# FPGA_PSIO.net
KiCad netlist of a schematic drawn in Altium Designer
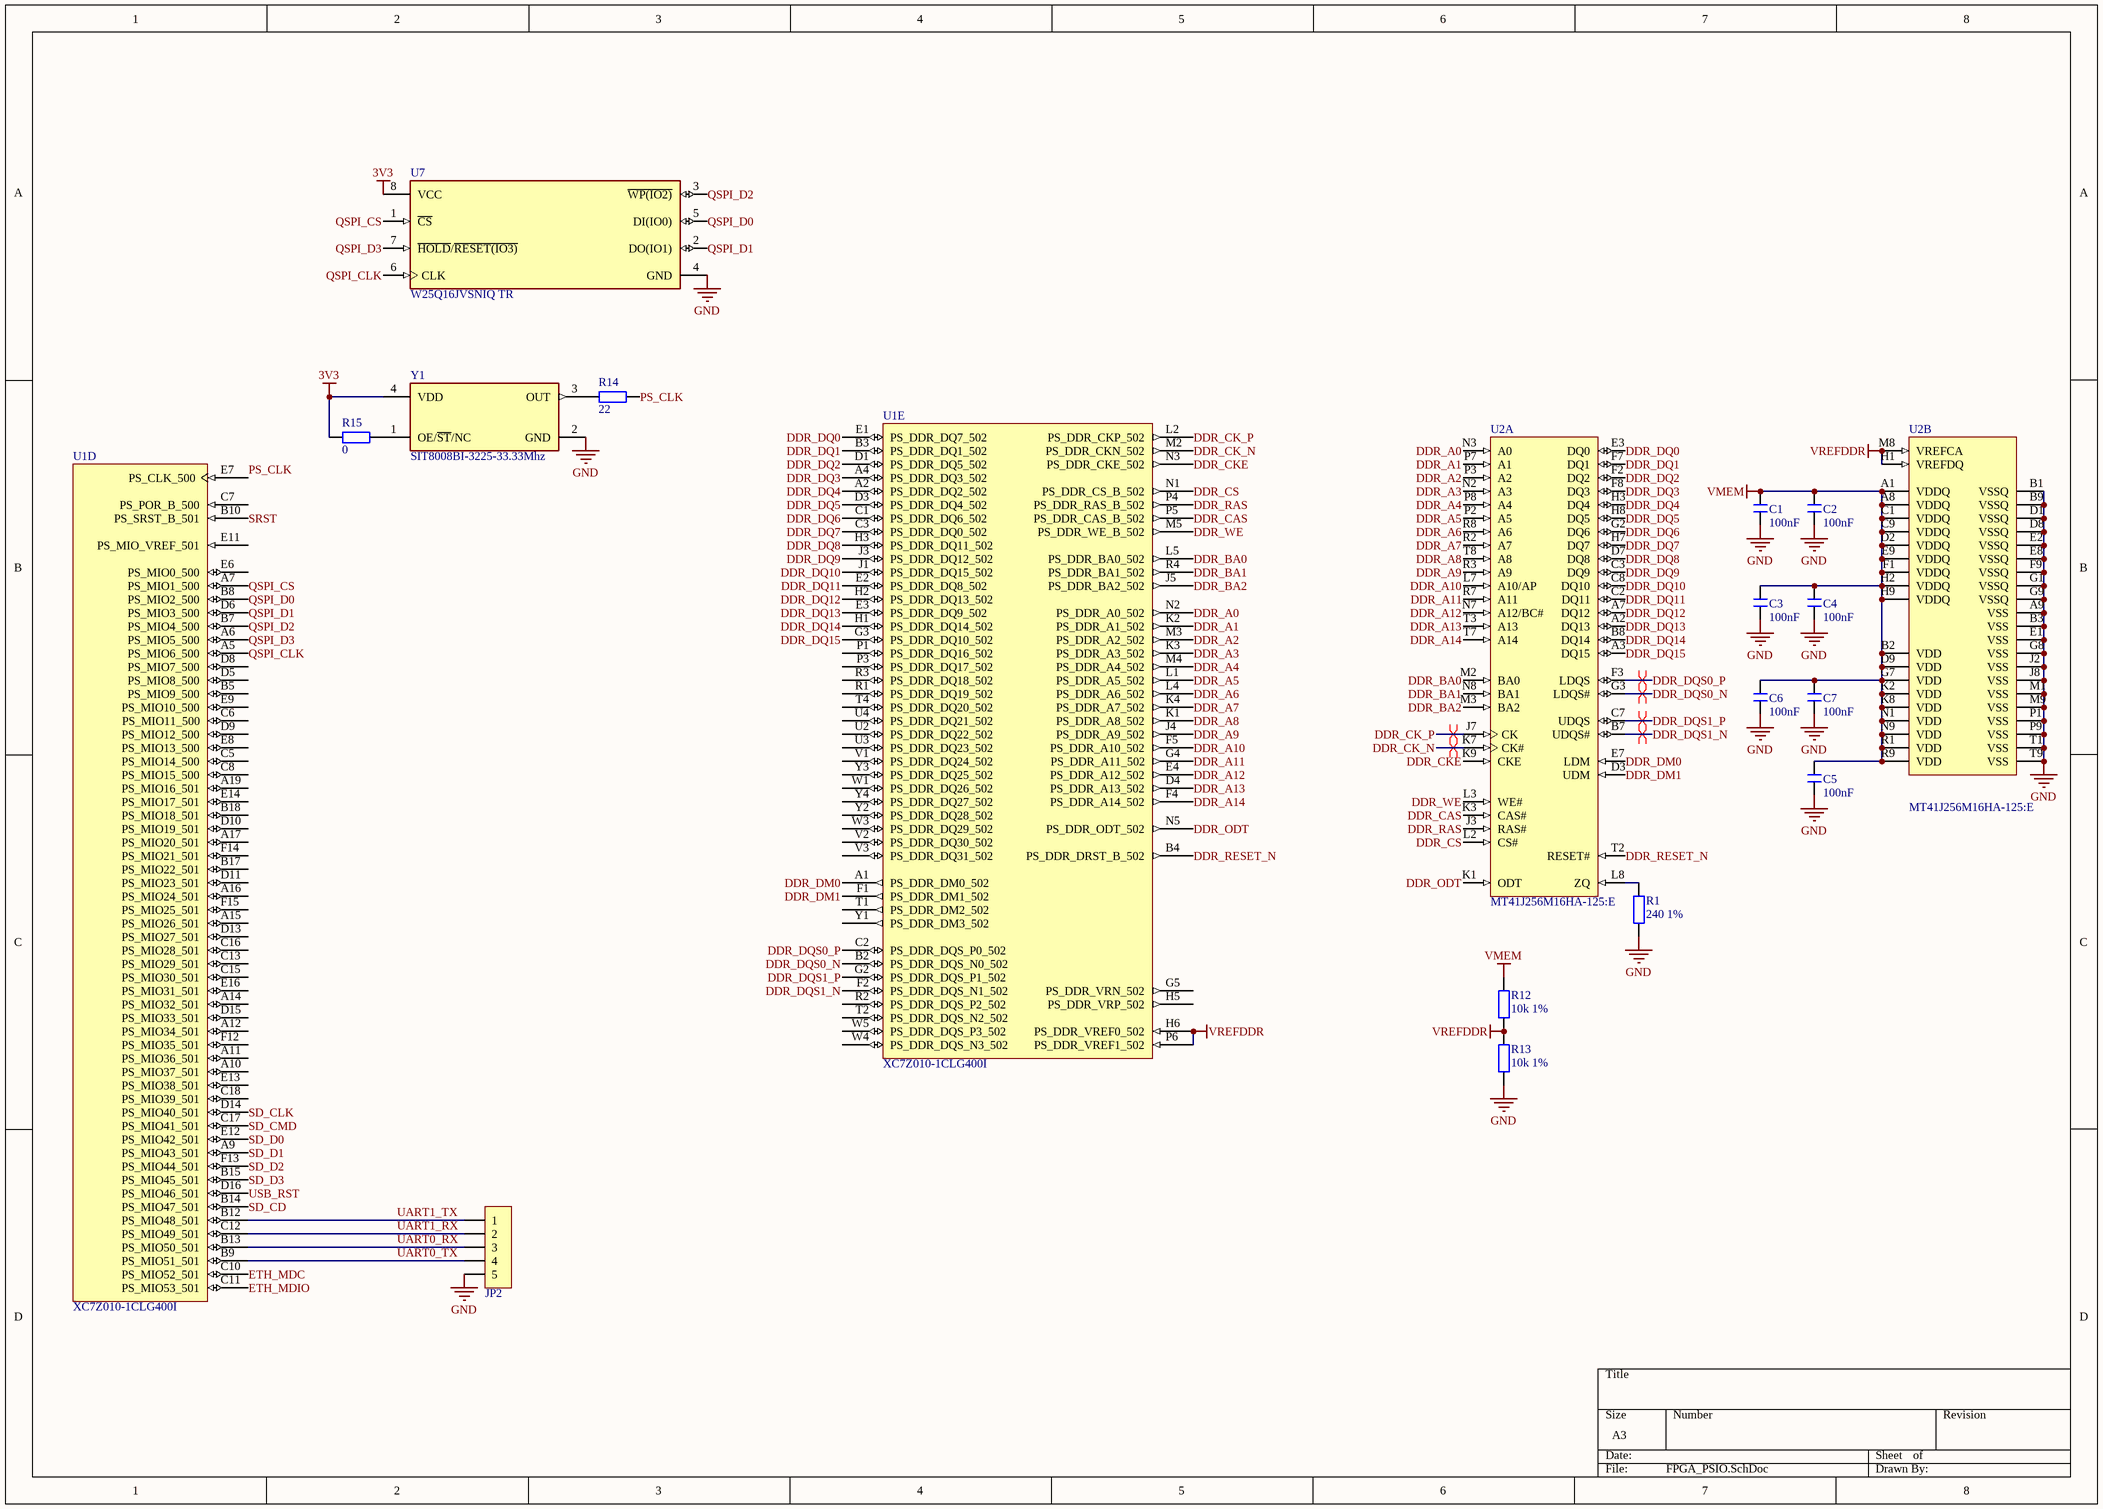
[diagram p0: FPGA_PSIO.SchDoc]

(export (version "E")
  (design (tool "Eeschema 10.0.6"))
  (components
    (comp (ref "C1") (value "100nF") (footprint "C0402") (libsource (lib "Passive") (part "C")))
    (comp (ref "C2") (value "100nF") (footprint "C0402") (libsource (lib "Passive") (part "C")))
    (comp (ref "C3") (value "100nF") (footprint "C0402") (libsource (lib "Passive") (part "C")))
    (comp (ref "C4") (value "100nF") (footprint "C0402") (libsource (lib "Passive") (part "C")))
    (comp (ref "C5") (value "100nF") (footprint "C0402") (libsource (lib "Passive") (part "C")))
    (comp (ref "C6") (value "100nF") (footprint "C0402") (libsource (lib "Passive") (part "C")))
    (comp (ref "C7") (value "100nF") (footprint "C0402") (libsource (lib "Passive") (part "C")))
    (comp (ref "JP2")
      (value "HDR-1X5")
      (footprint "HDR2.54-LI-5P")
      (description "5P接插件")
      (fields (field (name "版权归属") "源创客"))
      (libsource (lib "Pin2.54") (part "Header 5"))
    )
    (comp (ref "R1") (value "240 1%") (footprint "R0603") (libsource (lib "Passive") (part "R")))
    (comp (ref "R12") (value "10k 1%") (footprint "R0402") (libsource (lib "Passive") (part "R")))
    (comp (ref "R13") (value "10k 1%") (footprint "R0402") (libsource (lib "Passive") (part "R")))
    (comp (ref "R14") (value "22") (footprint "R0402") (libsource (lib "Passive") (part "R")))
    (comp (ref "R15") (value "0") (footprint "R0402") (libsource (lib "Passive") (part "R")))
    (comp (ref "U1")
      (value "XC7Z010-1CLG400I")
      (footprint "CLG400")
      (fields (field (name "GENERIC PART NUMBER") "XC7Z010"))
      (libsource (lib "Altium Content Vault") (part "XNLX-XC7Z010-CLG400"))
    )
    (comp (ref "U2")
      (value "MT41J256M16HA-125:E")
      (footprint "MICT-HA-96")
      (description "4 Gb DDR3-1600 SDRAM, 256 Mb x 16, 1.25 ns, 1.5 V, 0 to 95 degC, 96-Ball FBGA, Pb-Free")
      (fields (field (name "MANUFACTURER") "Micron"))
      (libsource (lib "Altium Content Vault") (part "MICT-MT41J256M16HA-96"))
    )
    (comp (ref "U7")
      (value "W25Q16JVSNIQ TR")
      (footprint "FP-SN-MFG")
      (description "IC FLASH 16MBIT SPI/QUAD 8SOIC")
      (libsource (lib "Altium Content Vault") (part "7098f54d44eb8b75f85f137256f9325"))
    )
    (comp (ref "Y1")
      (value "SIT8008BI-3225-33.33Mhz")
      (footprint "FP-SiT8008-2-MFG")
      (libsource (lib "Altium Content Vault") (part "5cf877c3599e51cbf79feac712dbb68"))
    )
  )
  (nets
    (net (code "2") (name "/DDR_A0") (class "Default")
      (node (ref "U1") (pin "N2") (pinfunction "PS_DDR_A0_502_N2") (pintype "output"))
      (node (ref "U2") (pin "N3") (pinfunction "A0_N3") (pintype "input"))
    )
    (net (code "3") (name "/DDR_A1") (class "Default")
      (node (ref "U1") (pin "K2") (pinfunction "PS_DDR_A1_502_K2") (pintype "output"))
      (node (ref "U2") (pin "P7") (pinfunction "A1_P7") (pintype "input"))
    )
    (net (code "4") (name "/DDR_A2") (class "Default")
      (node (ref "U1") (pin "M3") (pinfunction "PS_DDR_A2_502_M3") (pintype "output"))
      (node (ref "U2") (pin "P3") (pinfunction "A2_P3") (pintype "input"))
    )
    (net (code "5") (name "/DDR_A3") (class "Default")
      (node (ref "U1") (pin "K3") (pinfunction "PS_DDR_A3_502_K3") (pintype "output"))
      (node (ref "U2") (pin "N2") (pinfunction "A3_N2") (pintype "input"))
    )
    (net (code "6") (name "/DDR_A4") (class "Default")
      (node (ref "U1") (pin "M4") (pinfunction "PS_DDR_A4_502_M4") (pintype "output"))
      (node (ref "U2") (pin "P8") (pinfunction "A4_P8") (pintype "input"))
    )
    (net (code "7") (name "/DDR_A5") (class "Default")
      (node (ref "U1") (pin "L1") (pinfunction "PS_DDR_A5_502_L1") (pintype "output"))
      (node (ref "U2") (pin "P2") (pinfunction "A5_P2") (pintype "input"))
    )
    (net (code "8") (name "/DDR_A6") (class "Default")
      (node (ref "U1") (pin "L4") (pinfunction "PS_DDR_A6_502_L4") (pintype "output"))
      (node (ref "U2") (pin "R8") (pinfunction "A6_R8") (pintype "input"))
    )
    (net (code "9") (name "/DDR_A7") (class "Default")
      (node (ref "U1") (pin "K4") (pinfunction "PS_DDR_A7_502_K4") (pintype "output"))
      (node (ref "U2") (pin "R2") (pinfunction "A7_R2") (pintype "input"))
    )
    (net (code "10") (name "/DDR_A8") (class "Default")
      (node (ref "U1") (pin "K1") (pinfunction "PS_DDR_A8_502_K1") (pintype "output"))
      (node (ref "U2") (pin "T8") (pinfunction "A8_T8") (pintype "input"))
    )
    (net (code "11") (name "/DDR_A9") (class "Default")
      (node (ref "U1") (pin "J4") (pinfunction "PS_DDR_A9_502_J4") (pintype "output"))
      (node (ref "U2") (pin "R3") (pinfunction "A9_R3") (pintype "input"))
    )
    (net (code "12") (name "/DDR_A10") (class "Default")
      (node (ref "U1") (pin "F5") (pinfunction "PS_DDR_A10_502_F5") (pintype "output"))
      (node (ref "U2") (pin "L7") (pinfunction "A10/AP_L7") (pintype "input"))
    )
    (net (code "13") (name "/DDR_A11") (class "Default")
      (node (ref "U1") (pin "G4") (pinfunction "PS_DDR_A11_502_G4") (pintype "output"))
      (node (ref "U2") (pin "R7") (pinfunction "A11_R7") (pintype "input"))
    )
    (net (code "14") (name "/DDR_A12") (class "Default")
      (node (ref "U1") (pin "E4") (pinfunction "PS_DDR_A12_502_E4") (pintype "output"))
      (node (ref "U2") (pin "N7") (pinfunction "A12/BC#_N7") (pintype "input"))
    )
    (net (code "15") (name "/DDR_A13") (class "Default")
      (node (ref "U1") (pin "D4") (pinfunction "PS_DDR_A13_502_D4") (pintype "output"))
      (node (ref "U2") (pin "T3") (pinfunction "A13_T3") (pintype "input"))
    )
    (net (code "16") (name "/DDR_A14") (class "Default")
      (node (ref "U1") (pin "F4") (pinfunction "PS_DDR_A14_502_F4") (pintype "output"))
      (node (ref "U2") (pin "T7") (pinfunction "A14_T7") (pintype "input"))
    )
    (net (code "17") (name "/DDR_BA0") (class "Default")
      (node (ref "U1") (pin "L5") (pinfunction "PS_DDR_BA0_502_L5") (pintype "output"))
      (node (ref "U2") (pin "M2") (pinfunction "BA0_M2") (pintype "input"))
    )
    (net (code "18") (name "/DDR_BA1") (class "Default")
      (node (ref "U1") (pin "R4") (pinfunction "PS_DDR_BA1_502_R4") (pintype "output"))
      (node (ref "U2") (pin "N8") (pinfunction "BA1_N8") (pintype "input"))
    )
    (net (code "19") (name "/DDR_BA2") (class "Default")
      (node (ref "U1") (pin "J5") (pinfunction "PS_DDR_BA2_502_J5") (pintype "output"))
      (node (ref "U2") (pin "M3") (pinfunction "BA2_M3") (pintype "input"))
    )
    (net (code "20") (name "/DDR_CAS") (class "Default")
      (node (ref "U1") (pin "P5") (pinfunction "PS_DDR_CAS_B_502_P5") (pintype "output"))
      (node (ref "U2") (pin "K3") (pinfunction "CAS#_K3") (pintype "input"))
    )
    (net (code "21") (name "/DDR_CKE") (class "Default")
      (node (ref "U1") (pin "N3") (pinfunction "PS_DDR_CKE_502_N3") (pintype "output"))
      (node (ref "U2") (pin "K9") (pinfunction "CKE_K9") (pintype "input"))
    )
    (net (code "22") (name "/DDR_CK_N") (class "Default")
      (node (ref "U1") (pin "M2") (pinfunction "PS_DDR_CKN_502_M2") (pintype "output"))
      (node (ref "U2") (pin "K7") (pinfunction "CK#_K7") (pintype "input"))
    )
    (net (code "23") (name "/DDR_CK_P") (class "Default")
      (node (ref "U1") (pin "L2") (pinfunction "PS_DDR_CKP_502_L2") (pintype "output"))
      (node (ref "U2") (pin "J7") (pinfunction "CK_J7") (pintype "input"))
    )
    (net (code "24") (name "/DDR_CS") (class "Default")
      (node (ref "U1") (pin "N1") (pinfunction "PS_DDR_CS_B_502_N1") (pintype "output"))
      (node (ref "U2") (pin "L2") (pinfunction "CS#_L2") (pintype "input"))
    )
    (net (code "25") (name "/DDR_DM0") (class "Default")
      (node (ref "U1") (pin "A1") (pinfunction "PS_DDR_DM0_502_A1") (pintype "output"))
      (node (ref "U2") (pin "E7") (pinfunction "LDM_E7") (pintype "input"))
    )
    (net (code "26") (name "/DDR_DM1") (class "Default")
      (node (ref "U1") (pin "F1") (pinfunction "PS_DDR_DM1_502_F1") (pintype "output"))
      (node (ref "U2") (pin "D3") (pinfunction "UDM_D3") (pintype "input"))
    )
    (net (code "27") (name "/DDR_DQ0") (class "Default")
      (node (ref "U1") (pin "E1") (pinfunction "PS_DDR_DQ7_502_E1") (pintype "bidirectional"))
      (node (ref "U2") (pin "E3") (pinfunction "DQ0_E3") (pintype "bidirectional"))
    )
    (net (code "28") (name "/DDR_DQ1") (class "Default")
      (node (ref "U1") (pin "B3") (pinfunction "PS_DDR_DQ1_502_B3") (pintype "bidirectional"))
      (node (ref "U2") (pin "F7") (pinfunction "DQ1_F7") (pintype "bidirectional"))
    )
    (net (code "29") (name "/DDR_DQ2") (class "Default")
      (node (ref "U1") (pin "D1") (pinfunction "PS_DDR_DQ5_502_D1") (pintype "bidirectional"))
      (node (ref "U2") (pin "F2") (pinfunction "DQ2_F2") (pintype "bidirectional"))
    )
    (net (code "30") (name "/DDR_DQ3") (class "Default")
      (node (ref "U1") (pin "A4") (pinfunction "PS_DDR_DQ3_502_A4") (pintype "bidirectional"))
      (node (ref "U2") (pin "F8") (pinfunction "DQ3_F8") (pintype "bidirectional"))
    )
    (net (code "31") (name "/DDR_DQ4") (class "Default")
      (node (ref "U1") (pin "A2") (pinfunction "PS_DDR_DQ2_502_A2") (pintype "bidirectional"))
      (node (ref "U2") (pin "H3") (pinfunction "DQ4_H3") (pintype "bidirectional"))
    )
    (net (code "32") (name "/DDR_DQ5") (class "Default")
      (node (ref "U1") (pin "D3") (pinfunction "PS_DDR_DQ4_502_D3") (pintype "bidirectional"))
      (node (ref "U2") (pin "H8") (pinfunction "DQ5_H8") (pintype "bidirectional"))
    )
    (net (code "33") (name "/DDR_DQ6") (class "Default")
      (node (ref "U1") (pin "C1") (pinfunction "PS_DDR_DQ6_502_C1") (pintype "bidirectional"))
      (node (ref "U2") (pin "G2") (pinfunction "DQ6_G2") (pintype "bidirectional"))
    )
    (net (code "34") (name "/DDR_DQ7") (class "Default")
      (node (ref "U1") (pin "C3") (pinfunction "PS_DDR_DQ0_502_C3") (pintype "bidirectional"))
      (node (ref "U2") (pin "H7") (pinfunction "DQ7_H7") (pintype "bidirectional"))
    )
    (net (code "35") (name "/DDR_DQ8") (class "Default")
      (node (ref "U1") (pin "H3") (pinfunction "PS_DDR_DQ11_502_H3") (pintype "bidirectional"))
      (node (ref "U2") (pin "D7") (pinfunction "DQ8_D7") (pintype "bidirectional"))
    )
    (net (code "36") (name "/DDR_DQ9") (class "Default")
      (node (ref "U1") (pin "J3") (pinfunction "PS_DDR_DQ12_502_J3") (pintype "bidirectional"))
      (node (ref "U2") (pin "C3") (pinfunction "DQ9_C3") (pintype "bidirectional"))
    )
    (net (code "37") (name "/DDR_DQ10") (class "Default")
      (node (ref "U1") (pin "J1") (pinfunction "PS_DDR_DQ15_502_J1") (pintype "bidirectional"))
      (node (ref "U2") (pin "C8") (pinfunction "DQ10_C8") (pintype "bidirectional"))
    )
    (net (code "38") (name "/DDR_DQ11") (class "Default")
      (node (ref "U1") (pin "E2") (pinfunction "PS_DDR_DQ8_502_E2") (pintype "bidirectional"))
      (node (ref "U2") (pin "C2") (pinfunction "DQ11_C2") (pintype "bidirectional"))
    )
    (net (code "39") (name "/DDR_DQ12") (class "Default")
      (node (ref "U1") (pin "H2") (pinfunction "PS_DDR_DQ13_502_H2") (pintype "bidirectional"))
      (node (ref "U2") (pin "A7") (pinfunction "DQ12_A7") (pintype "bidirectional"))
    )
    (net (code "40") (name "/DDR_DQ13") (class "Default")
      (node (ref "U1") (pin "E3") (pinfunction "PS_DDR_DQ9_502_E3") (pintype "bidirectional"))
      (node (ref "U2") (pin "A2") (pinfunction "DQ13_A2") (pintype "bidirectional"))
    )
    (net (code "41") (name "/DDR_DQ14") (class "Default")
      (node (ref "U1") (pin "H1") (pinfunction "PS_DDR_DQ14_502_H1") (pintype "bidirectional"))
      (node (ref "U2") (pin "B8") (pinfunction "DQ14_B8") (pintype "bidirectional"))
    )
    (net (code "42") (name "/DDR_DQ15") (class "Default")
      (node (ref "U1") (pin "G3") (pinfunction "PS_DDR_DQ10_502_G3") (pintype "bidirectional"))
      (node (ref "U2") (pin "A3") (pinfunction "DQ15_A3") (pintype "bidirectional"))
    )
    (net (code "43") (name "/DDR_DQS0_N") (class "Default")
      (node (ref "U1") (pin "B2") (pinfunction "PS_DDR_DQS_N0_502_B2") (pintype "bidirectional"))
      (node (ref "U2") (pin "G3") (pinfunction "LDQS#_G3") (pintype "bidirectional"))
    )
    (net (code "44") (name "/DDR_DQS0_P") (class "Default")
      (node (ref "U1") (pin "C2") (pinfunction "PS_DDR_DQS_P0_502_C2") (pintype "bidirectional"))
      (node (ref "U2") (pin "F3") (pinfunction "LDQS_F3") (pintype "bidirectional"))
    )
    (net (code "45") (name "/DDR_DQS1_N") (class "Default")
      (node (ref "U1") (pin "F2") (pinfunction "PS_DDR_DQS_N1_502_F2") (pintype "bidirectional"))
      (node (ref "U2") (pin "B7") (pinfunction "UDQS#_B7") (pintype "bidirectional"))
    )
    (net (code "46") (name "/DDR_DQS1_P") (class "Default")
      (node (ref "U1") (pin "G2") (pinfunction "PS_DDR_DQS_P1_502_G2") (pintype "bidirectional"))
      (node (ref "U2") (pin "C7") (pinfunction "UDQS_C7") (pintype "bidirectional"))
    )
    (net (code "47") (name "/DDR_ODT") (class "Default")
      (node (ref "U1") (pin "N5") (pinfunction "PS_DDR_ODT_502_N5") (pintype "output"))
      (node (ref "U2") (pin "K1") (pinfunction "ODT_K1") (pintype "input"))
    )
    (net (code "48") (name "/DDR_RAS") (class "Default")
      (node (ref "U1") (pin "P4") (pinfunction "PS_DDR_RAS_B_502_P4") (pintype "output"))
      (node (ref "U2") (pin "J3") (pinfunction "RAS#_J3") (pintype "input"))
    )
    (net (code "49") (name "/DDR_RESET_N") (class "Default")
      (node (ref "U1") (pin "B4") (pinfunction "PS_DDR_DRST_B_502_B4") (pintype "output"))
      (node (ref "U2") (pin "T2") (pinfunction "RESET#_T2") (pintype "input"))
    )
    (net (code "50") (name "/DDR_WE") (class "Default")
      (node (ref "U1") (pin "M5") (pinfunction "PS_DDR_WE_B_502_M5") (pintype "output"))
      (node (ref "U2") (pin "L3") (pinfunction "WE#_L3") (pintype "input"))
    )
    (net (code "51") (name "/ETH_MDC") (class "Default")
      (node (ref "U1") (pin "C10") (pinfunction "PS_MIO52_501_C10") (pintype "bidirectional"))
    )
    (net (code "52") (name "/ETH_MDIO") (class "Default")
      (node (ref "U1") (pin "C11") (pinfunction "PS_MIO53_501_C11") (pintype "bidirectional"))
    )
    (net (code "53") (name "/PS_CLK") (class "Default")
      (node (ref "R14") (pin "1") (pinfunction "1_1") (pintype "passive"))
      (node (ref "U1") (pin "E7") (pinfunction "PS_CLK_500_E7") (pintype "input"))
    )
    (net (code "54") (name "/QSPI_CLK") (class "Default")
      (node (ref "U1") (pin "A5") (pinfunction "PS_MIO6_500_A5") (pintype "bidirectional"))
      (node (ref "U7") (pin "6") (pinfunction "CLK_6") (pintype "input"))
    )
    (net (code "55") (name "/QSPI_CS") (class "Default")
      (node (ref "U1") (pin "A7") (pinfunction "PS_MIO1_500_A7") (pintype "bidirectional"))
      (node (ref "U7") (pin "1") (pinfunction "~{CS}_1") (pintype "input"))
    )
    (net (code "56") (name "/QSPI_D0") (class "Default")
      (node (ref "U1") (pin "B8") (pinfunction "PS_MIO2_500_B8") (pintype "bidirectional"))
      (node (ref "U7") (pin "5") (pinfunction "DI(IO0)_5") (pintype "bidirectional"))
    )
    (net (code "57") (name "/QSPI_D1") (class "Default")
      (node (ref "U1") (pin "D6") (pinfunction "PS_MIO3_500_D6") (pintype "bidirectional"))
      (node (ref "U7") (pin "2") (pinfunction "DO(IO1)_2") (pintype "bidirectional"))
    )
    (net (code "58") (name "/QSPI_D2") (class "Default")
      (node (ref "U1") (pin "B7") (pinfunction "PS_MIO4_500_B7") (pintype "bidirectional"))
      (node (ref "U7") (pin "3") (pinfunction "~{WP(IO2)}_3") (pintype "bidirectional"))
    )
    (net (code "59") (name "/QSPI_D3") (class "Default")
      (node (ref "U1") (pin "A6") (pinfunction "PS_MIO5_500_A6") (pintype "bidirectional"))
      (node (ref "U7") (pin "7") (pinfunction "~{HOLD}/~{RESET(IO3)}_7") (pintype "input"))
    )
    (net (code "60") (name "/SD_CD") (class "Default")
      (node (ref "U1") (pin "B14") (pinfunction "PS_MIO47_501_B14") (pintype "bidirectional"))
    )
    (net (code "61") (name "/SD_CLK") (class "Default")
      (node (ref "U1") (pin "D14") (pinfunction "PS_MIO40_501_D14") (pintype "bidirectional"))
    )
    (net (code "62") (name "/SD_CMD") (class "Default")
      (node (ref "U1") (pin "C17") (pinfunction "PS_MIO41_501_C17") (pintype "bidirectional"))
    )
    (net (code "63") (name "/SD_D0") (class "Default")
      (node (ref "U1") (pin "E12") (pinfunction "PS_MIO42_501_E12") (pintype "bidirectional"))
    )
    (net (code "64") (name "/SD_D1") (class "Default")
      (node (ref "U1") (pin "A9") (pinfunction "PS_MIO43_501_A9") (pintype "bidirectional"))
    )
    (net (code "65") (name "/SD_D2") (class "Default")
      (node (ref "U1") (pin "F13") (pinfunction "PS_MIO44_501_F13") (pintype "bidirectional"))
    )
    (net (code "66") (name "/SD_D3") (class "Default")
      (node (ref "U1") (pin "B15") (pinfunction "PS_MIO45_501_B15") (pintype "bidirectional"))
    )
    (net (code "67") (name "/SRST") (class "Default")
      (node (ref "U1") (pin "B10") (pinfunction "PS_SRST_B_501_B10") (pintype "input"))
    )
    (net (code "68") (name "/UART0_RX") (class "Default")
      (node (ref "JP2") (pin "3") (pinfunction "3_3") (pintype "passive"))
      (node (ref "U1") (pin "B13") (pinfunction "PS_MIO50_501_B13") (pintype "bidirectional"))
    )
    (net (code "69") (name "/UART0_TX") (class "Default")
      (node (ref "JP2") (pin "4") (pinfunction "4_4") (pintype "passive"))
      (node (ref "U1") (pin "B9") (pinfunction "PS_MIO51_501_B9") (pintype "bidirectional"))
    )
    (net (code "70") (name "/UART1_RX") (class "Default")
      (node (ref "JP2") (pin "2") (pinfunction "2_2") (pintype "passive"))
      (node (ref "U1") (pin "C12") (pinfunction "PS_MIO49_501_C12") (pintype "bidirectional"))
    )
    (net (code "71") (name "/UART1_TX") (class "Default")
      (node (ref "JP2") (pin "1") (pinfunction "1_1") (pintype "passive"))
      (node (ref "U1") (pin "B12") (pinfunction "PS_MIO48_501_B12") (pintype "bidirectional"))
    )
    (net (code "72") (name "/USB_RST") (class "Default")
      (node (ref "U1") (pin "D16") (pinfunction "PS_MIO46_501_D16") (pintype "bidirectional"))
    )
    (net (code "73") (name "3V3") (class "Default")
      (node (ref "R15") (pin "1") (pinfunction "1_1") (pintype "passive"))
      (node (ref "U7") (pin "8") (pinfunction "VCC_8") (pintype "power_in"))
      (node (ref "Y1") (pin "4") (pinfunction "VDD_4") (pintype "power_in"))
    )
    (net (code "74") (name "GND") (class "Default")
      (node (ref "C1") (pin "2") (pinfunction "2_2") (pintype "passive"))
      (node (ref "C2") (pin "2") (pinfunction "2_2") (pintype "passive"))
      (node (ref "C3") (pin "2") (pinfunction "2_2") (pintype "passive"))
      (node (ref "C4") (pin "2") (pinfunction "2_2") (pintype "passive"))
      (node (ref "C5") (pin "2") (pinfunction "2_2") (pintype "passive"))
      (node (ref "C6") (pin "2") (pinfunction "2_2") (pintype "passive"))
      (node (ref "C7") (pin "2") (pinfunction "2_2") (pintype "passive"))
      (node (ref "JP2") (pin "5") (pinfunction "5_5") (pintype "passive"))
      (node (ref "R1") (pin "1") (pinfunction "1_1") (pintype "passive"))
      (node (ref "R13") (pin "1") (pinfunction "1_1") (pintype "passive"))
      (node (ref "U2") (pin "A9") (pinfunction "VSS_A9") (pintype "power_in"))
      (node (ref "U2") (pin "B1") (pinfunction "VSSQ_B1") (pintype "power_in"))
      (node (ref "U2") (pin "B3") (pinfunction "VSS_B3") (pintype "power_in"))
      (node (ref "U2") (pin "B9") (pinfunction "VSSQ_B9") (pintype "power_in"))
      (node (ref "U2") (pin "D1") (pinfunction "VSSQ_D1") (pintype "power_in"))
      (node (ref "U2") (pin "D8") (pinfunction "VSSQ_D8") (pintype "power_in"))
      (node (ref "U2") (pin "E1") (pinfunction "VSS_E1") (pintype "power_in"))
      (node (ref "U2") (pin "E2") (pinfunction "VSSQ_E2") (pintype "power_in"))
      (node (ref "U2") (pin "E8") (pinfunction "VSSQ_E8") (pintype "power_in"))
      (node (ref "U2") (pin "F9") (pinfunction "VSSQ_F9") (pintype "power_in"))
      (node (ref "U2") (pin "G1") (pinfunction "VSSQ_G1") (pintype "power_in"))
      (node (ref "U2") (pin "G8") (pinfunction "VSS_G8") (pintype "power_in"))
      (node (ref "U2") (pin "G9") (pinfunction "VSSQ_G9") (pintype "power_in"))
      (node (ref "U2") (pin "J2") (pinfunction "VSS_J2") (pintype "power_in"))
      (node (ref "U2") (pin "J8") (pinfunction "VSS_J8") (pintype "power_in"))
      (node (ref "U2") (pin "M1") (pinfunction "VSS_M1") (pintype "power_in"))
      (node (ref "U2") (pin "M9") (pinfunction "VSS_M9") (pintype "power_in"))
      (node (ref "U2") (pin "P1") (pinfunction "VSS_P1") (pintype "power_in"))
      (node (ref "U2") (pin "P9") (pinfunction "VSS_P9") (pintype "power_in"))
      (node (ref "U2") (pin "T1") (pinfunction "VSS_T1") (pintype "power_in"))
      (node (ref "U2") (pin "T9") (pinfunction "VSS_T9") (pintype "power_in"))
      (node (ref "U7") (pin "4") (pinfunction "GND_4") (pintype "power_in"))
      (node (ref "Y1") (pin "2") (pinfunction "GND_2") (pintype "power_in"))
    )
    (net (code "75") (name "Net-(U2A-ZQ)") (class "Default")
      (node (ref "R1") (pin "2") (pinfunction "2_2") (pintype "passive"))
      (node (ref "U2") (pin "L8") (pinfunction "ZQ_L8") (pintype "input"))
    )
    (net (code "76") (name "Net-(Y1-OE{slash}~{ST}{slash}NC)") (class "Default")
      (node (ref "R15") (pin "2") (pinfunction "2_2") (pintype "passive"))
      (node (ref "Y1") (pin "1") (pinfunction "OE/~{ST}/NC_1") (pintype "passive"))
    )
    (net (code "77") (name "Net-(Y1-OUT)") (class "Default")
      (node (ref "R14") (pin "2") (pinfunction "2_2") (pintype "passive"))
      (node (ref "Y1") (pin "3") (pinfunction "OUT_3") (pintype "output"))
    )
    (net (code "78") (name "VMEM") (class "Default")
      (node (ref "C1") (pin "1") (pinfunction "1_1") (pintype "passive"))
      (node (ref "C2") (pin "1") (pinfunction "1_1") (pintype "passive"))
      (node (ref "C3") (pin "1") (pinfunction "1_1") (pintype "passive"))
      (node (ref "C4") (pin "1") (pinfunction "1_1") (pintype "passive"))
      (node (ref "C5") (pin "1") (pinfunction "1_1") (pintype "passive"))
      (node (ref "C6") (pin "1") (pinfunction "1_1") (pintype "passive"))
      (node (ref "C7") (pin "1") (pinfunction "1_1") (pintype "passive"))
      (node (ref "R12") (pin "2") (pinfunction "2_2") (pintype "passive"))
      (node (ref "U2") (pin "A1") (pinfunction "VDDQ_A1") (pintype "power_in"))
      (node (ref "U2") (pin "A8") (pinfunction "VDDQ_A8") (pintype "power_in"))
      (node (ref "U2") (pin "B2") (pinfunction "VDD_B2") (pintype "power_in"))
      (node (ref "U2") (pin "C1") (pinfunction "VDDQ_C1") (pintype "power_in"))
      (node (ref "U2") (pin "C9") (pinfunction "VDDQ_C9") (pintype "power_in"))
      (node (ref "U2") (pin "D2") (pinfunction "VDDQ_D2") (pintype "power_in"))
      (node (ref "U2") (pin "D9") (pinfunction "VDD_D9") (pintype "power_in"))
      (node (ref "U2") (pin "E9") (pinfunction "VDDQ_E9") (pintype "power_in"))
      (node (ref "U2") (pin "F1") (pinfunction "VDDQ_F1") (pintype "power_in"))
      (node (ref "U2") (pin "G7") (pinfunction "VDD_G7") (pintype "power_in"))
      (node (ref "U2") (pin "H2") (pinfunction "VDDQ_H2") (pintype "power_in"))
      (node (ref "U2") (pin "H9") (pinfunction "VDDQ_H9") (pintype "power_in"))
      (node (ref "U2") (pin "K2") (pinfunction "VDD_K2") (pintype "power_in"))
      (node (ref "U2") (pin "K8") (pinfunction "VDD_K8") (pintype "power_in"))
      (node (ref "U2") (pin "N1") (pinfunction "VDD_N1") (pintype "power_in"))
      (node (ref "U2") (pin "N9") (pinfunction "VDD_N9") (pintype "power_in"))
      (node (ref "U2") (pin "R1") (pinfunction "VDD_R1") (pintype "power_in"))
      (node (ref "U2") (pin "R9") (pinfunction "VDD_R9") (pintype "power_in"))
    )
    (net (code "79") (name "VREFDDR") (class "Default")
      (node (ref "R12") (pin "1") (pinfunction "1_1") (pintype "passive"))
      (node (ref "R13") (pin "2") (pinfunction "2_2") (pintype "passive"))
      (node (ref "U1") (pin "H6") (pinfunction "PS_DDR_VREF0_502_H6") (pintype "input"))
      (node (ref "U1") (pin "P6") (pinfunction "PS_DDR_VREF1_502_P6") (pintype "input"))
      (node (ref "U2") (pin "H1") (pinfunction "VREFDQ_H1") (pintype "input"))
      (node (ref "U2") (pin "M8") (pinfunction "VREFCA_M8") (pintype "input"))
    )
    (net (code "80") (name "unconnected-(U1D-PS_MIO0_500-PadE6)") (class "Default")
      (node (ref "U1") (pin "E6") (pinfunction "PS_MIO0_500_E6") (pintype "bidirectional"))
    )
    (net (code "81") (name "unconnected-(U1D-PS_MIO7_500-PadD8)") (class "Default")
      (node (ref "U1") (pin "D8") (pinfunction "PS_MIO7_500_D8") (pintype "bidirectional"))
    )
    (net (code "82") (name "unconnected-(U1D-PS_MIO8_500-PadD5)") (class "Default")
      (node (ref "U1") (pin "D5") (pinfunction "PS_MIO8_500_D5") (pintype "bidirectional"))
    )
    (net (code "83") (name "unconnected-(U1D-PS_MIO9_500-PadB5)") (class "Default")
      (node (ref "U1") (pin "B5") (pinfunction "PS_MIO9_500_B5") (pintype "bidirectional"))
    )
    (net (code "84") (name "unconnected-(U1D-PS_MIO10_500-PadE9)") (class "Default")
      (node (ref "U1") (pin "E9") (pinfunction "PS_MIO10_500_E9") (pintype "bidirectional"))
    )
    (net (code "85") (name "unconnected-(U1D-PS_MIO11_500-PadC6)") (class "Default")
      (node (ref "U1") (pin "C6") (pinfunction "PS_MIO11_500_C6") (pintype "bidirectional"))
    )
    (net (code "86") (name "unconnected-(U1D-PS_MIO12_500-PadD9)") (class "Default")
      (node (ref "U1") (pin "D9") (pinfunction "PS_MIO12_500_D9") (pintype "bidirectional"))
    )
    (net (code "87") (name "unconnected-(U1D-PS_MIO13_500-PadE8)") (class "Default")
      (node (ref "U1") (pin "E8") (pinfunction "PS_MIO13_500_E8") (pintype "bidirectional"))
    )
    (net (code "88") (name "unconnected-(U1D-PS_MIO14_500-PadC5)") (class "Default")
      (node (ref "U1") (pin "C5") (pinfunction "PS_MIO14_500_C5") (pintype "bidirectional"))
    )
    (net (code "89") (name "unconnected-(U1D-PS_MIO15_500-PadC8)") (class "Default")
      (node (ref "U1") (pin "C8") (pinfunction "PS_MIO15_500_C8") (pintype "bidirectional"))
    )
    (net (code "90") (name "unconnected-(U1D-PS_MIO16_501-PadA19)") (class "Default")
      (node (ref "U1") (pin "A19") (pinfunction "PS_MIO16_501_A19") (pintype "bidirectional"))
    )
    (net (code "91") (name "unconnected-(U1D-PS_MIO17_501-PadE14)") (class "Default")
      (node (ref "U1") (pin "E14") (pinfunction "PS_MIO17_501_E14") (pintype "bidirectional"))
    )
    (net (code "92") (name "unconnected-(U1D-PS_MIO18_501-PadB18)") (class "Default")
      (node (ref "U1") (pin "B18") (pinfunction "PS_MIO18_501_B18") (pintype "bidirectional"))
    )
    (net (code "93") (name "unconnected-(U1D-PS_MIO19_501-PadD10)") (class "Default")
      (node (ref "U1") (pin "D10") (pinfunction "PS_MIO19_501_D10") (pintype "bidirectional"))
    )
    (net (code "94") (name "unconnected-(U1D-PS_MIO20_501-PadA17)") (class "Default")
      (node (ref "U1") (pin "A17") (pinfunction "PS_MIO20_501_A17") (pintype "bidirectional"))
    )
    (net (code "95") (name "unconnected-(U1D-PS_MIO21_501-PadF14)") (class "Default")
      (node (ref "U1") (pin "F14") (pinfunction "PS_MIO21_501_F14") (pintype "bidirectional"))
    )
    (net (code "96") (name "unconnected-(U1D-PS_MIO22_501-PadB17)") (class "Default")
      (node (ref "U1") (pin "B17") (pinfunction "PS_MIO22_501_B17") (pintype "bidirectional"))
    )
    (net (code "97") (name "unconnected-(U1D-PS_MIO23_501-PadD11)") (class "Default")
      (node (ref "U1") (pin "D11") (pinfunction "PS_MIO23_501_D11") (pintype "bidirectional"))
    )
    (net (code "98") (name "unconnected-(U1D-PS_MIO24_501-PadA16)") (class "Default")
      (node (ref "U1") (pin "A16") (pinfunction "PS_MIO24_501_A16") (pintype "bidirectional"))
    )
    (net (code "99") (name "unconnected-(U1D-PS_MIO25_501-PadF15)") (class "Default")
      (node (ref "U1") (pin "F15") (pinfunction "PS_MIO25_501_F15") (pintype "bidirectional"))
    )
    (net (code "100") (name "unconnected-(U1D-PS_MIO26_501-PadA15)") (class "Default")
      (node (ref "U1") (pin "A15") (pinfunction "PS_MIO26_501_A15") (pintype "bidirectional"))
    )
    (net (code "101") (name "unconnected-(U1D-PS_MIO27_501-PadD13)") (class "Default")
      (node (ref "U1") (pin "D13") (pinfunction "PS_MIO27_501_D13") (pintype "bidirectional"))
    )
    (net (code "102") (name "unconnected-(U1D-PS_MIO28_501-PadC16)") (class "Default")
      (node (ref "U1") (pin "C16") (pinfunction "PS_MIO28_501_C16") (pintype "bidirectional"))
    )
    (net (code "103") (name "unconnected-(U1D-PS_MIO29_501-PadC13)") (class "Default")
      (node (ref "U1") (pin "C13") (pinfunction "PS_MIO29_501_C13") (pintype "bidirectional"))
    )
    (net (code "104") (name "unconnected-(U1D-PS_MIO30_501-PadC15)") (class "Default")
      (node (ref "U1") (pin "C15") (pinfunction "PS_MIO30_501_C15") (pintype "bidirectional"))
    )
    (net (code "105") (name "unconnected-(U1D-PS_MIO31_501-PadE16)") (class "Default")
      (node (ref "U1") (pin "E16") (pinfunction "PS_MIO31_501_E16") (pintype "bidirectional"))
    )
    (net (code "106") (name "unconnected-(U1D-PS_MIO32_501-PadA14)") (class "Default")
      (node (ref "U1") (pin "A14") (pinfunction "PS_MIO32_501_A14") (pintype "bidirectional"))
    )
    (net (code "107") (name "unconnected-(U1D-PS_MIO33_501-PadD15)") (class "Default")
      (node (ref "U1") (pin "D15") (pinfunction "PS_MIO33_501_D15") (pintype "bidirectional"))
    )
    (net (code "108") (name "unconnected-(U1D-PS_MIO34_501-PadA12)") (class "Default")
      (node (ref "U1") (pin "A12") (pinfunction "PS_MIO34_501_A12") (pintype "bidirectional"))
    )
    (net (code "109") (name "unconnected-(U1D-PS_MIO35_501-PadF12)") (class "Default")
      (node (ref "U1") (pin "F12") (pinfunction "PS_MIO35_501_F12") (pintype "bidirectional"))
    )
    (net (code "110") (name "unconnected-(U1D-PS_MIO36_501-PadA11)") (class "Default")
      (node (ref "U1") (pin "A11") (pinfunction "PS_MIO36_501_A11") (pintype "bidirectional"))
    )
    (net (code "111") (name "unconnected-(U1D-PS_MIO37_501-PadA10)") (class "Default")
      (node (ref "U1") (pin "A10") (pinfunction "PS_MIO37_501_A10") (pintype "bidirectional"))
    )
    (net (code "112") (name "unconnected-(U1D-PS_MIO38_501-PadE13)") (class "Default")
      (node (ref "U1") (pin "E13") (pinfunction "PS_MIO38_501_E13") (pintype "bidirectional"))
    )
    (net (code "113") (name "unconnected-(U1D-PS_MIO39_501-PadC18)") (class "Default")
      (node (ref "U1") (pin "C18") (pinfunction "PS_MIO39_501_C18") (pintype "bidirectional"))
    )
    (net (code "114") (name "unconnected-(U1D-PS_MIO_VREF_501-PadE11)") (class "Default")
      (node (ref "U1") (pin "E11") (pinfunction "PS_MIO_VREF_501_E11") (pintype "input"))
    )
    (net (code "115") (name "unconnected-(U1D-PS_POR_B_500-PadC7)") (class "Default")
      (node (ref "U1") (pin "C7") (pinfunction "PS_POR_B_500_C7") (pintype "input"))
    )
    (net (code "116") (name "unconnected-(U1E-PS_DDR_DM2_502-PadT1)") (class "Default")
      (node (ref "U1") (pin "T1") (pinfunction "PS_DDR_DM2_502_T1") (pintype "output"))
    )
    (net (code "117") (name "unconnected-(U1E-PS_DDR_DM3_502-PadY1)") (class "Default")
      (node (ref "U1") (pin "Y1") (pinfunction "PS_DDR_DM3_502_Y1") (pintype "output"))
    )
    (net (code "118") (name "unconnected-(U1E-PS_DDR_DQ16_502-PadP1)") (class "Default")
      (node (ref "U1") (pin "P1") (pinfunction "PS_DDR_DQ16_502_P1") (pintype "bidirectional"))
    )
    (net (code "119") (name "unconnected-(U1E-PS_DDR_DQ17_502-PadP3)") (class "Default")
      (node (ref "U1") (pin "P3") (pinfunction "PS_DDR_DQ17_502_P3") (pintype "bidirectional"))
    )
    (net (code "120") (name "unconnected-(U1E-PS_DDR_DQ18_502-PadR3)") (class "Default")
      (node (ref "U1") (pin "R3") (pinfunction "PS_DDR_DQ18_502_R3") (pintype "bidirectional"))
    )
    (net (code "121") (name "unconnected-(U1E-PS_DDR_DQ19_502-PadR1)") (class "Default")
      (node (ref "U1") (pin "R1") (pinfunction "PS_DDR_DQ19_502_R1") (pintype "bidirectional"))
    )
    (net (code "122") (name "unconnected-(U1E-PS_DDR_DQ20_502-PadT4)") (class "Default")
      (node (ref "U1") (pin "T4") (pinfunction "PS_DDR_DQ20_502_T4") (pintype "bidirectional"))
    )
    (net (code "123") (name "unconnected-(U1E-PS_DDR_DQ21_502-PadU4)") (class "Default")
      (node (ref "U1") (pin "U4") (pinfunction "PS_DDR_DQ21_502_U4") (pintype "bidirectional"))
    )
    (net (code "124") (name "unconnected-(U1E-PS_DDR_DQ22_502-PadU2)") (class "Default")
      (node (ref "U1") (pin "U2") (pinfunction "PS_DDR_DQ22_502_U2") (pintype "bidirectional"))
    )
    (net (code "125") (name "unconnected-(U1E-PS_DDR_DQ23_502-PadU3)") (class "Default")
      (node (ref "U1") (pin "U3") (pinfunction "PS_DDR_DQ23_502_U3") (pintype "bidirectional"))
    )
    (net (code "126") (name "unconnected-(U1E-PS_DDR_DQ24_502-PadV1)") (class "Default")
      (node (ref "U1") (pin "V1") (pinfunction "PS_DDR_DQ24_502_V1") (pintype "bidirectional"))
    )
    (net (code "127") (name "unconnected-(U1E-PS_DDR_DQ25_502-PadY3)") (class "Default")
      (node (ref "U1") (pin "Y3") (pinfunction "PS_DDR_DQ25_502_Y3") (pintype "bidirectional"))
    )
    (net (code "128") (name "unconnected-(U1E-PS_DDR_DQ26_502-PadW1)") (class "Default")
      (node (ref "U1") (pin "W1") (pinfunction "PS_DDR_DQ26_502_W1") (pintype "bidirectional"))
    )
    (net (code "129") (name "unconnected-(U1E-PS_DDR_DQ27_502-PadY4)") (class "Default")
      (node (ref "U1") (pin "Y4") (pinfunction "PS_DDR_DQ27_502_Y4") (pintype "bidirectional"))
    )
    (net (code "130") (name "unconnected-(U1E-PS_DDR_DQ28_502-PadY2)") (class "Default")
      (node (ref "U1") (pin "Y2") (pinfunction "PS_DDR_DQ28_502_Y2") (pintype "bidirectional"))
    )
    (net (code "131") (name "unconnected-(U1E-PS_DDR_DQ29_502-PadW3)") (class "Default")
      (node (ref "U1") (pin "W3") (pinfunction "PS_DDR_DQ29_502_W3") (pintype "bidirectional"))
    )
    (net (code "132") (name "unconnected-(U1E-PS_DDR_DQ30_502-PadV2)") (class "Default")
      (node (ref "U1") (pin "V2") (pinfunction "PS_DDR_DQ30_502_V2") (pintype "bidirectional"))
    )
    (net (code "133") (name "unconnected-(U1E-PS_DDR_DQ31_502-PadV3)") (class "Default")
      (node (ref "U1") (pin "V3") (pinfunction "PS_DDR_DQ31_502_V3") (pintype "bidirectional"))
    )
    (net (code "134") (name "unconnected-(U1E-PS_DDR_DQS_N2_502-PadT2)") (class "Default")
      (node (ref "U1") (pin "T2") (pinfunction "PS_DDR_DQS_N2_502_T2") (pintype "bidirectional"))
    )
    (net (code "135") (name "unconnected-(U1E-PS_DDR_DQS_N3_502-PadW4)") (class "Default")
      (node (ref "U1") (pin "W4") (pinfunction "PS_DDR_DQS_N3_502_W4") (pintype "bidirectional"))
    )
    (net (code "136") (name "unconnected-(U1E-PS_DDR_DQS_P2_502-PadR2)") (class "Default")
      (node (ref "U1") (pin "R2") (pinfunction "PS_DDR_DQS_P2_502_R2") (pintype "bidirectional"))
    )
    (net (code "137") (name "unconnected-(U1E-PS_DDR_DQS_P3_502-PadW5)") (class "Default")
      (node (ref "U1") (pin "W5") (pinfunction "PS_DDR_DQS_P3_502_W5") (pintype "bidirectional"))
    )
    (net (code "138") (name "unconnected-(U1E-PS_DDR_VRN_502-PadG5)") (class "Default")
      (node (ref "U1") (pin "G5") (pinfunction "PS_DDR_VRN_502_G5") (pintype "output"))
    )
    (net (code "139") (name "unconnected-(U1E-PS_DDR_VRP_502-PadH5)") (class "Default")
      (node (ref "U1") (pin "H5") (pinfunction "PS_DDR_VRP_502_H5") (pintype "output"))
    )
  )
)
